# Power.net
KiCad netlist of a schematic drawn in Altium Designer
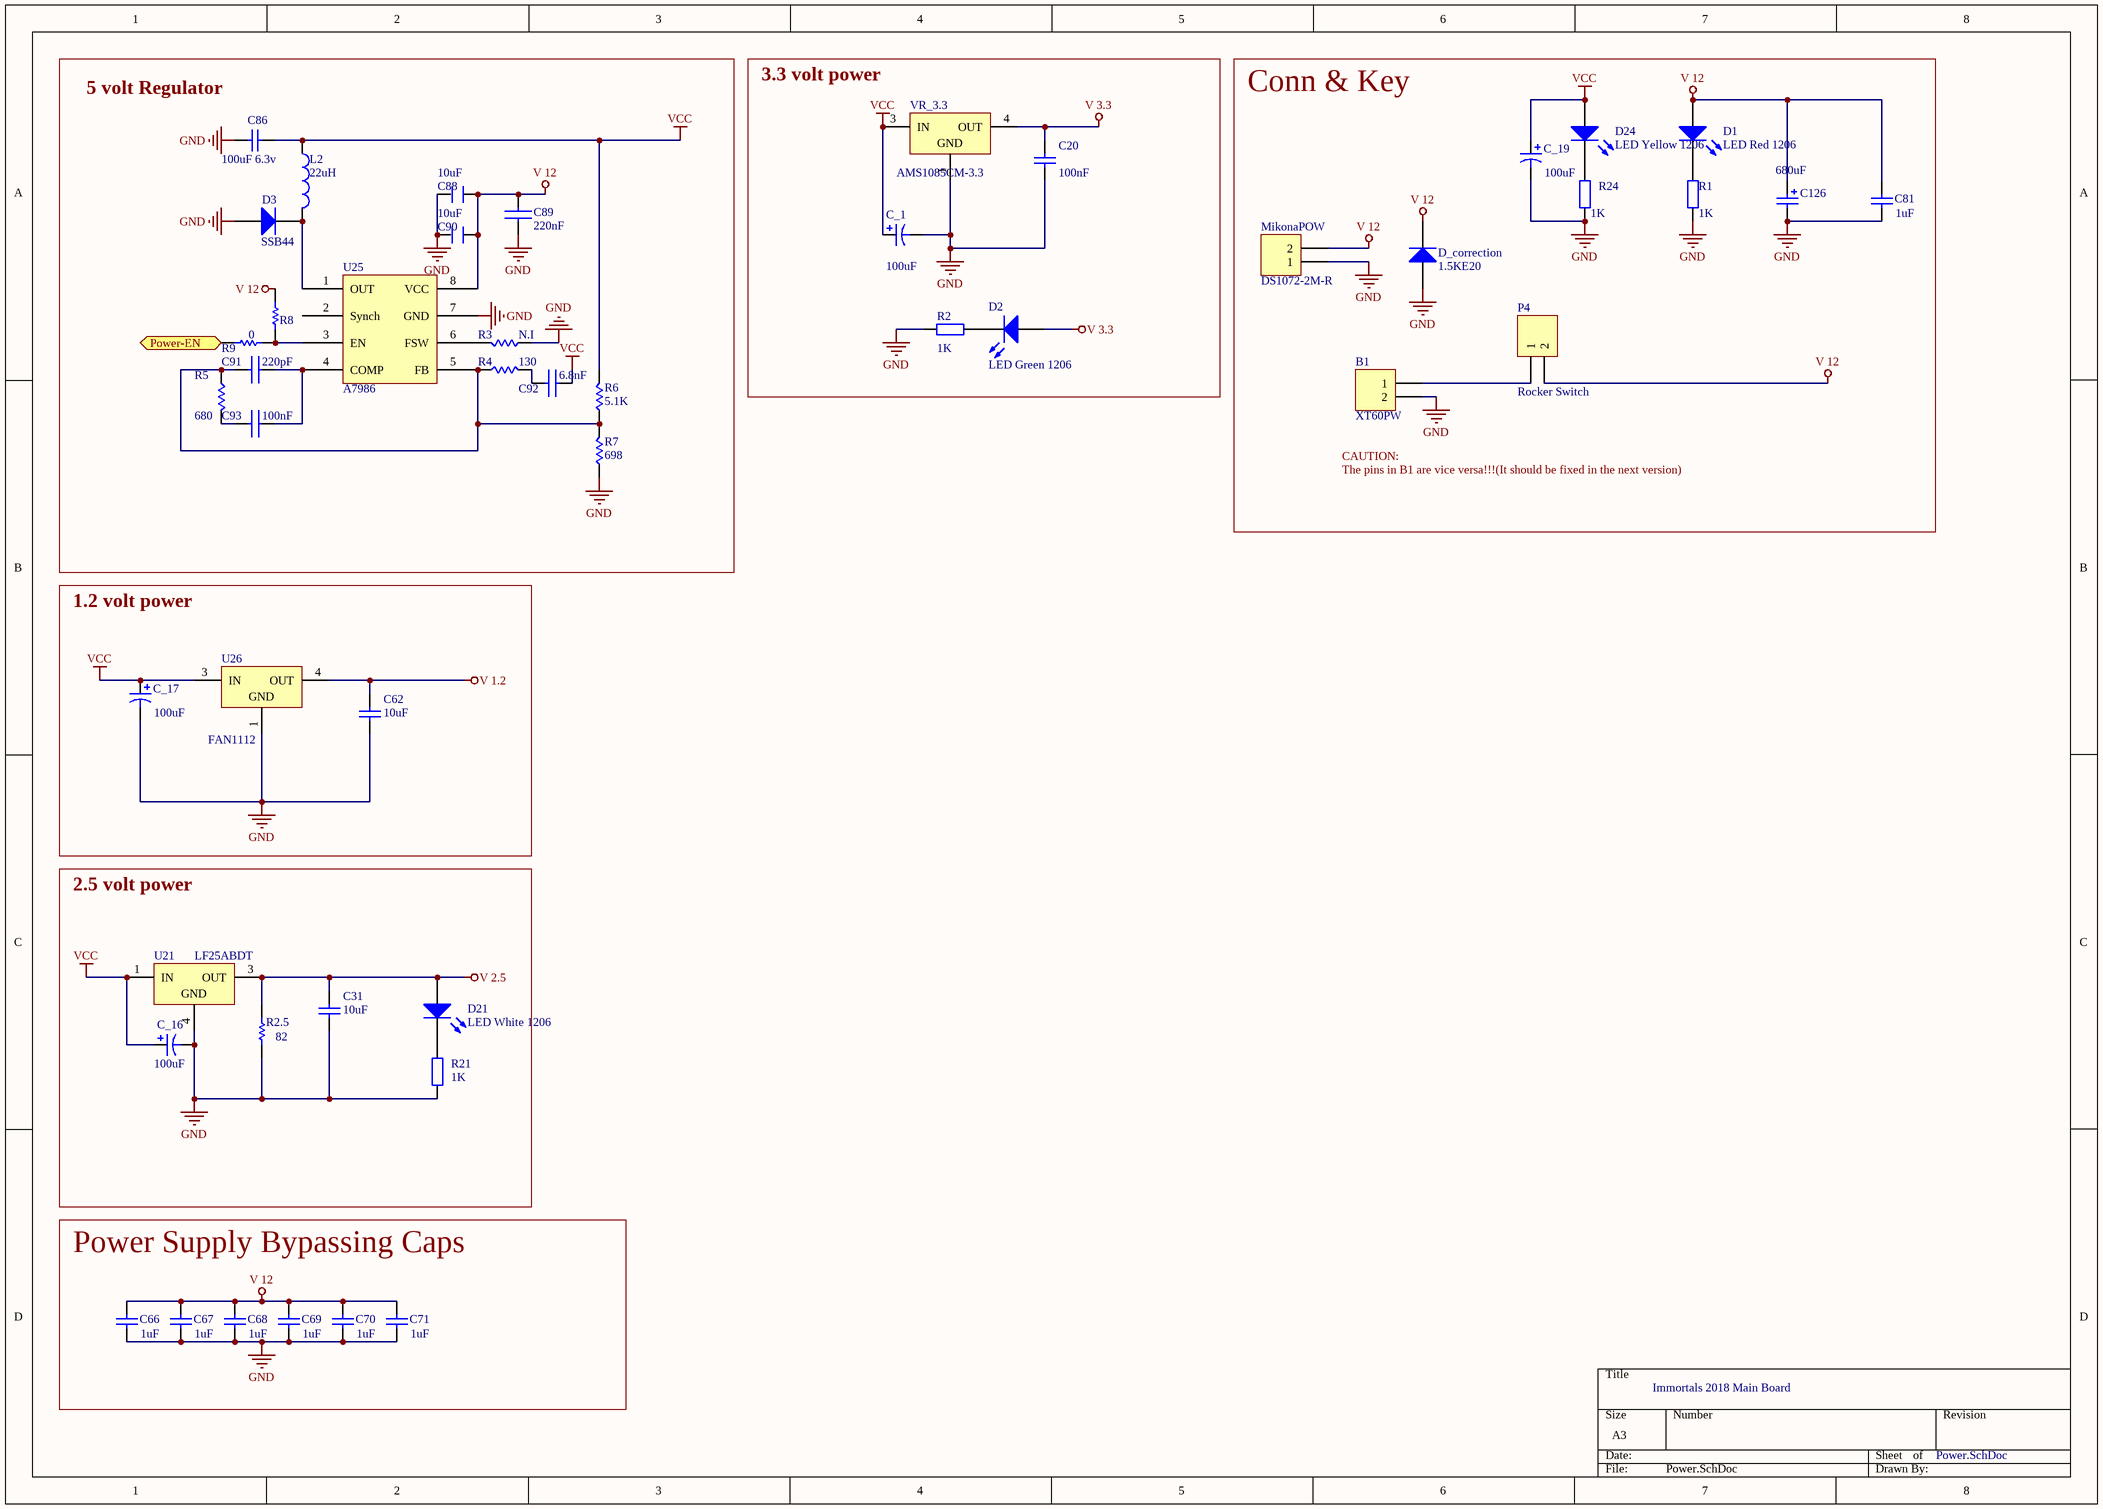
[diagram p0: Power.SchDoc]

(export (version "E")
  (design (tool "Eeschema 10.0.6"))
  (components
    (comp (ref "B1")
      (value "XT60PW")
      (footprint "XT60PW")
      (description "Power Connector")
      (fields (field (name "PUBLISHER") "Altium Limited"))
      (libsource (lib "REV(5)") (part "XT60PW"))
    )
    (comp (ref "C20")
      (value "100nF")
      (footprint "C1206")
      (description "Capacitor (Semiconductor SIM Model)")
      (fields (field (name "Comment") "Cap 100nF 1206") (field (name "PUBLISHER") "Altium Limited"))
      (libsource (lib "Miscellaneous Devices") (part "Cap Semi"))
    )
    (comp (ref "C31")
      (value "10uF")
      (footprint "C1206")
      (description "Capacitor (Semiconductor SIM Model)")
      (fields (field (name "Comment") "Cap 10uF 1206") (field (name "PUBLISHER") "Altium Limited"))
      (libsource (lib "Miscellaneous Devices") (part "Cap Semi"))
    )
    (comp (ref "C62")
      (value "10uF")
      (footprint "C1206")
      (description "Capacitor (Semiconductor SIM Model)")
      (fields (field (name "Comment") "Cap 10uF 1206") (field (name "PUBLISHER") "Altium Limited"))
      (libsource (lib "Miscellaneous Devices") (part "Cap Semi"))
    )
    (comp (ref "C66")
      (value "1uF")
      (footprint "C0805")
      (description "Capacitor")
      (fields (field (name "Comment") "Cap 1uF 0805"))
      (libsource (lib "Altium Nanoboard Project") (part "CAP"))
    )
    (comp (ref "C67")
      (value "1uF")
      (footprint "C0805")
      (description "Capacitor")
      (fields (field (name "Comment") "Cap 1uF 0805"))
      (libsource (lib "Altium Nanoboard Project") (part "CAP"))
    )
    (comp (ref "C68")
      (value "1uF")
      (footprint "C0805")
      (description "Capacitor")
      (fields (field (name "Comment") "Cap 1uF 0805"))
      (libsource (lib "Altium Nanoboard Project") (part "CAP"))
    )
    (comp (ref "C69")
      (value "1uF")
      (footprint "C0805")
      (description "Capacitor")
      (fields (field (name "Comment") "Cap 1uF 0805"))
      (libsource (lib "Altium Nanoboard Project") (part "CAP"))
    )
    (comp (ref "C70")
      (value "1uF")
      (footprint "C0805")
      (description "Capacitor")
      (fields (field (name "Comment") "Cap 1uF 0805"))
      (libsource (lib "Altium Nanoboard Project") (part "CAP"))
    )
    (comp (ref "C71")
      (value "1uF")
      (footprint "C0805")
      (description "Capacitor")
      (fields (field (name "Comment") "Cap 1uF 0805"))
      (libsource (lib "Altium Nanoboard Project") (part "CAP"))
    )
    (comp (ref "C81")
      (value "1uF")
      (footprint "C0805")
      (description "Capacitor")
      (fields (field (name "Comment") "Cap 1uF 0805"))
      (libsource (lib "Altium Nanoboard Project") (part "CAP"))
    )
    (comp (ref "C86")
      (value "100uF 6.3v")
      (footprint "C1210")
      (description "Capacitor (Semiconductor SIM Model)")
      (fields (field (name "Comment") "Cap 100uF 1210") (field (name "PUBLISHER") "Altium Limited"))
      (libsource (lib "Miscellaneous Devices") (part "Cap Semi"))
    )
    (comp (ref "C88")
      (value "10uF")
      (footprint "C[0805]")
      (description "Cap , SMD")
      (fields (field (name "Comment") "Cap 10uF 0805"))
      (libsource (lib "TCU Control") (part "C"))
    )
    (comp (ref "C89")
      (value "220nF")
      (footprint "C0603")
      (description "C0603")
      (fields (field (name "Comment") "Cap 220nF 0603"))
      (libsource (lib "My SMD Lib") (part "Cap 0603"))
    )
    (comp (ref "C90")
      (value "10uF")
      (footprint "C[0805]")
      (description "Cap , SMD")
      (fields (field (name "Comment") "Cap 10uF 0805"))
      (libsource (lib "TCU Control") (part "C"))
    )
    (comp (ref "C91")
      (value "220pF")
      (footprint "C0603")
      (description "C0603")
      (fields (field (name "Comment") "Cap 220pF 0603"))
      (libsource (lib "My SMD Lib") (part "Cap 0603"))
    )
    (comp (ref "C92")
      (value "6.8nF")
      (footprint "C0603")
      (description "C0603")
      (fields (field (name "Comment") "Cap 6.8nF 0603"))
      (libsource (lib "") (part "Cap 0603_1"))
    )
    (comp (ref "C93")
      (value "100nF")
      (footprint "C0603")
      (description "Cap SMD 0603")
      (fields (field (name "Comment") "Cap 100nF 0603"))
      (libsource (lib "My SMD Lib") (part "Cap 0603"))
    )
    (comp (ref "C126")
      (value "680uF")
      (footprint "CAPPR5-5x5")
      (description "Polarized Capacitor (Radial)")
      (fields (field (name "Comment") "Cap 680uF dip") (field (name "PUBLISHER") "Altium Limited"))
      (libsource (lib "REV(5)") (part "Cap Pol1"))
    )
    (comp (ref "C_1")
      (value "100uF")
      (footprint "6332[2512]")
      (description "Polarized Capacitor (Surface Mount)")
      (fields (field (name "Comment") "Cap 100uF 2512") (field (name "PUBLISHER") "Altium Limited"))
      (libsource (lib "Miscellaneous Devices") (part "Cap Pol3"))
    )
    (comp (ref "C_16")
      (value "100uF")
      (footprint "6332[2512]")
      (description "Polarized Capacitor (Surface Mount)")
      (fields (field (name "Comment") "Cap 100uF 2512") (field (name "PUBLISHER") "Altium Limited"))
      (libsource (lib "Miscellaneous Devices") (part "Cap Pol3"))
    )
    (comp (ref "C_17")
      (value "100uF")
      (footprint "6332[2512]")
      (description "Polarized Capacitor (Surface Mount)")
      (fields (field (name "Comment") "Cap 100uF 2512") (field (name "PUBLISHER") "Altium Limited"))
      (libsource (lib "Miscellaneous Devices") (part "Cap Pol3"))
    )
    (comp (ref "C_19")
      (value "100uF")
      (footprint "6332[2512]")
      (description "Polarized Capacitor (Surface Mount)")
      (fields (field (name "Comment") "Cap 100uF 2512") (field (name "PUBLISHER") "Altium Limited"))
      (libsource (lib "Miscellaneous Devices") (part "Cap Pol3"))
    )
    (comp (ref "D1")
      (value "LED Red 1206")
      (footprint "REV(5):3.2X1.6X1.1 - RED")
      (description "Typical RED, GREEN, YELLOW, AMBER GaAs LED")
      (fields (field (name "PUBLISHER") "Altium Limited"))
      (libsource (lib "Miscellaneous Devices") (part "LED2"))
    )
    (comp (ref "D2")
      (value "LED Green 1206")
      (footprint "REV(5):3.2X1.6X1.1 - GREEN")
      (description "Typical RED, GREEN, YELLOW, AMBER GaAs LED")
      (fields (field (name "PUBLISHER") "Altium Limited"))
      (libsource (lib "Miscellaneous Devices") (part "LED2"))
    )
    (comp (ref "D3")
      (value "SSB44")
      (footprint "DIOM4336X24N")
      (description "1 Amp General Purpose Rectifier")
      (fields (field (name "PUBLISHER") "Altium Limited"))
      (libsource (lib "REV(5)") (part "Diode SSB44"))
    )
    (comp (ref "D21")
      (value "LED White 1206")
      (footprint "REV(5):3.2X1.6X1.1 - WHITE")
      (description "Typical RED, GREEN, YELLOW, AMBER GaAs LED")
      (fields (field (name "PUBLISHER") "Altium Limited"))
      (libsource (lib "Miscellaneous Devices") (part "LED2"))
    )
    (comp (ref "D24")
      (value "LED Yellow 1206")
      (footprint "REV(5):3.2X1.6X1.1 - YELLOW")
      (description "Typical RED, GREEN, YELLOW, AMBER GaAs LED")
      (fields (field (name "PUBLISHER") "Altium Limited"))
      (libsource (lib "Miscellaneous Devices") (part "LED2"))
    )
    (comp (ref "D_correction")
      (value "1.5KE20")
      (footprint "DO-41")
      (description "1 Amp General Purpose Rectifier")
      (fields (field (name "PUBLISHER") "Altium Limited"))
      (libsource (lib "REV(5)") (part "Diode 1N4001"))
    )
    (comp (ref "L2")
      (value "22uH")
      (footprint "INDP110100X50N")
      (fields (field (name "Comment") "Inductor 22uH"))
      (libsource (lib "REV(5)") (part "7447714220 WE-PD SMD"))
    )
    (comp (ref "MikonaPOW")
      (value "DS1072-2M-R")
      (footprint "DS1072-2M&F-R")
      (description "Right Angle 3.96mm Power pin")
      (fields (field (name "PUBLISHER") "Altium Limited"))
      (libsource (lib "REV(5)") (part "Header 2"))
    )
    (comp (ref "P4")
      (value "Rocker Switch")
      (footprint "Rocker_SW")
      (description "I/O Power Switch")
      (fields (field (name "PUBLISHER") "Altium Limited"))
      (libsource (lib "REV(5)") (part "Rocker_SW"))
    )
    (comp (ref "R1")
      (value "1K")
      (footprint "2012[0805]")
      (description "Resistor")
      (fields (field (name "Comment") "Res 1K 0805") (field (name "PUBLISHER") "Altium Limited"))
      (libsource (lib "Miscellaneous Devices") (part "Res2"))
    )
    (comp (ref "R2")
      (value "1K")
      (footprint "2012[0805]")
      (description "Resistor")
      (fields (field (name "Comment") "Res 1K 0805") (field (name "PUBLISHER") "Altium Limited"))
      (libsource (lib "") (part "Res2_2"))
    )
    (comp (ref "R2.5")
      (value "82")
      (footprint "3216[1206]")
      (description "Semiconductor Resistor")
      (fields (field (name "Comment") "Res 82 1206") (field (name "PUBLISHER") "Altium Limited"))
      (libsource (lib "Miscellaneous Devices") (part "Res Semi"))
    )
    (comp (ref "R3")
      (value "N.I")
      (footprint "R0603")
      (description "Res 0603")
      (libsource (lib "My SMD Lib") (part "Res 0603"))
    )
    (comp (ref "R4")
      (value "130")
      (footprint "R0603")
      (description "Res 0603")
      (fields (field (name "Comment") "Res 130 0603"))
      (libsource (lib "My SMD Lib") (part "Res 0603"))
    )
    (comp (ref "R5")
      (value "680")
      (footprint "R0603")
      (description "Res 0603")
      (fields (field (name "Comment") "Res 680 0603"))
      (libsource (lib "My SMD Lib") (part "Res 0603"))
    )
    (comp (ref "R6")
      (value "5.1K")
      (footprint "R0603")
      (description "Res 0603")
      (fields (field (name "Comment") "Res 5.1K 0603"))
      (libsource (lib "My SMD Lib") (part "Res 0603"))
    )
    (comp (ref "R7")
      (value "698")
      (footprint "R0603")
      (description "Res 0603")
      (fields (field (name "Comment") "Res 698 0603"))
      (libsource (lib "My SMD Lib") (part "Res 0603"))
    )
    (comp (ref "R8")
      (value "N.I")
      (footprint "R0603")
      (description "Res 0603")
      (libsource (lib "SamatecLib") (part "R0603"))
    )
    (comp (ref "R9")
      (value "0")
      (footprint "R0603")
      (description "Res 0603")
      (fields (field (name "Comment") "Res 0 0603"))
      (libsource (lib "SamatecLib") (part "R0603"))
    )
    (comp (ref "R21")
      (value "1K")
      (footprint "2012[0805]")
      (description "Resistor")
      (fields (field (name "Comment") "Res 1K 0805") (field (name "PUBLISHER") "Altium Limited"))
      (libsource (lib "") (part "Res2_1"))
    )
    (comp (ref "R24")
      (value "1K")
      (footprint "2012[0805]")
      (description "Resistor")
      (fields (field (name "Comment") "Res 1K 0805") (field (name "PUBLISHER") "Altium Limited"))
      (libsource (lib "") (part "Res2_1"))
    )
    (comp (ref "U21")
      (value "LF25ABDT")
      (footprint "TO-252")
      (description "500mA, Very Low Drop (0.45V) Voltage Regulator")
      (fields (field (name "PUBLISHER") "Altium Limited"))
      (libsource (lib "REV(5)") (part "LF25ABDT"))
    )
    (comp (ref "U25")
      (value "A7986")
      (footprint "HSOP8")
      (description "DC\\DC Regulator")
      (libsource (lib "SamatecLib") (part "A7986"))
    )
    (comp (ref "U26")
      (value "FAN1112")
      (footprint "TO-252")
      (description "500mA, Very Low Drop (0.45V) Voltage Regulator")
      (fields (field (name "PUBLISHER") "Altium Limited"))
      (libsource (lib "REV(5)") (part "FAN1112"))
    )
    (comp (ref "VR_3.3")
      (value "AMS1085CM-3.3")
      (footprint "936-03")
      (description "5A Low Dropout Fast Response Positive Fixed Voltage Regulator")
      (fields (field (name "PUBLISHER") "Altium Limited"))
      (libsource (lib "REV(5)") (part "LT1585ACM-1.5"))
    )
  )
  (nets
    (net (code "1") (name "/Power-EN") (class "Default")
      (node (ref "R9") (pin "1") (pinfunction "1_1") (pintype "passive"))
    )
    (net (code "2") (name "GND") (class "Default")
      (node (ref "B1") (pin "2") (pinfunction "2_2") (pintype "passive"))
      (node (ref "C126") (pin "2") (pinfunction "2_2") (pintype "passive"))
      (node (ref "C20") (pin "2") (pinfunction "2_2") (pintype "passive"))
      (node (ref "C31") (pin "1") (pinfunction "1_1") (pintype "passive"))
      (node (ref "C62") (pin "1") (pinfunction "1_1") (pintype "passive"))
      (node (ref "C66") (pin "2") (pinfunction "2_2") (pintype "passive"))
      (node (ref "C67") (pin "2") (pinfunction "2_2") (pintype "passive"))
      (node (ref "C68") (pin "2") (pinfunction "2_2") (pintype "passive"))
      (node (ref "C69") (pin "2") (pinfunction "2_2") (pintype "passive"))
      (node (ref "C70") (pin "2") (pinfunction "2_2") (pintype "passive"))
      (node (ref "C71") (pin "2") (pinfunction "2_2") (pintype "passive"))
      (node (ref "C81") (pin "2") (pinfunction "2_2") (pintype "passive"))
      (node (ref "C86") (pin "1") (pinfunction "1_1") (pintype "passive"))
      (node (ref "C88") (pin "2") (pinfunction "2_2") (pintype "passive"))
      (node (ref "C89") (pin "2") (pinfunction "2_2") (pintype "passive"))
      (node (ref "C90") (pin "2") (pinfunction "2_2") (pintype "passive"))
      (node (ref "C_1") (pin "2") (pinfunction "2_2") (pintype "passive"))
      (node (ref "C_16") (pin "2") (pinfunction "2_2") (pintype "passive"))
      (node (ref "C_17") (pin "2") (pinfunction "2_2") (pintype "passive"))
      (node (ref "C_19") (pin "2") (pinfunction "2_2") (pintype "passive"))
      (node (ref "D3") (pin "2") (pinfunction "A_2") (pintype "passive"))
      (node (ref "D_correction") (pin "1") (pinfunction "A_1") (pintype "passive"))
      (node (ref "MikonaPOW") (pin "1") (pinfunction "1_1") (pintype "passive"))
      (node (ref "R1") (pin "2") (pinfunction "2_2") (pintype "passive"))
      (node (ref "R2") (pin "1") (pinfunction "1_1") (pintype "passive"))
      (node (ref "R2.5") (pin "1") (pinfunction "1_1") (pintype "passive"))
      (node (ref "R21") (pin "1") (pinfunction "1_1") (pintype "passive"))
      (node (ref "R24") (pin "1") (pinfunction "1_1") (pintype "passive"))
      (node (ref "R3") (pin "1") (pinfunction "1_1") (pintype "passive"))
      (node (ref "R7") (pin "1") (pinfunction "1_1") (pintype "passive"))
      (node (ref "U21") (pin "4") (pinfunction "GND_4") (pintype "power_in"))
      (node (ref "U25") (pin "7") (pinfunction "GND_7") (pintype "passive"))
      (node (ref "U26") (pin "1") (pinfunction "GND_1") (pintype "power_in"))
      (node (ref "VR_3.3") (pin "1") (pinfunction "GND_1") (pintype "power_in"))
    )
    (net (code "3") (name "Net-(B1-Pad1)") (class "Default")
      (node (ref "B1") (pin "1") (pinfunction "1_1") (pintype "passive"))
      (node (ref "P4") (pin "1") (pinfunction "1_1") (pintype "passive"))
    )
    (net (code "4") (name "Net-(C92-1-Pad2)") (class "Default")
      (node (ref "C92") (pin "2") (pinfunction "1_2") (pintype "passive"))
      (node (ref "R4") (pin "2") (pinfunction "2_2") (pintype "passive"))
    )
    (net (code "5") (name "Net-(C93-Pad1)") (class "Default")
      (node (ref "C93") (pin "1") (pinfunction "1_1") (pintype "passive"))
      (node (ref "R5") (pin "2") (pinfunction "2_2") (pintype "passive"))
    )
    (net (code "6") (name "Net-(D1-K)") (class "Default")
      (node (ref "D1") (pin "2") (pinfunction "K_2") (pintype "passive"))
      (node (ref "R1") (pin "1") (pinfunction "1_1") (pintype "passive"))
    )
    (net (code "7") (name "Net-(D2-K)") (class "Default")
      (node (ref "D2") (pin "2") (pinfunction "K_2") (pintype "passive"))
      (node (ref "R2") (pin "2") (pinfunction "2_2") (pintype "passive"))
    )
    (net (code "8") (name "Net-(D3-K)") (class "Default")
      (node (ref "D3") (pin "1") (pinfunction "K_1") (pintype "passive"))
      (node (ref "L2") (pin "2") (pinfunction "2_2") (pintype "passive"))
      (node (ref "U25") (pin "1") (pinfunction "OUT_1") (pintype "passive"))
    )
    (net (code "9") (name "Net-(D21-K)") (class "Default")
      (node (ref "D21") (pin "2") (pinfunction "K_2") (pintype "passive"))
      (node (ref "R21") (pin "2") (pinfunction "2_2") (pintype "passive"))
    )
    (net (code "10") (name "Net-(D24-K)") (class "Default")
      (node (ref "D24") (pin "2") (pinfunction "K_2") (pintype "passive"))
      (node (ref "R24") (pin "2") (pinfunction "2_2") (pintype "passive"))
    )
    (net (code "11") (name "Net-(U25-COMP)") (class "Default")
      (node (ref "C91") (pin "2") (pinfunction "2_2") (pintype "passive"))
      (node (ref "C93") (pin "2") (pinfunction "2_2") (pintype "passive"))
      (node (ref "U25") (pin "4") (pinfunction "COMP_4") (pintype "passive"))
    )
    (net (code "12") (name "Net-(U25-EN)") (class "Default")
      (node (ref "R8") (pin "2") (pinfunction "2_2") (pintype "passive"))
      (node (ref "R9") (pin "2") (pinfunction "2_2") (pintype "passive"))
      (node (ref "U25") (pin "3") (pinfunction "EN_3") (pintype "passive"))
    )
    (net (code "13") (name "Net-(U25-FB)") (class "Default")
      (node (ref "C91") (pin "1") (pinfunction "1_1") (pintype "passive"))
      (node (ref "R4") (pin "1") (pinfunction "1_1") (pintype "passive"))
      (node (ref "R5") (pin "1") (pinfunction "1_1") (pintype "passive"))
      (node (ref "R6") (pin "1") (pinfunction "1_1") (pintype "passive"))
      (node (ref "R7") (pin "2") (pinfunction "2_2") (pintype "passive"))
      (node (ref "U25") (pin "5") (pinfunction "FB_5") (pintype "passive"))
    )
    (net (code "14") (name "Net-(U25-FSW)") (class "Default")
      (node (ref "R3") (pin "2") (pinfunction "2_2") (pintype "passive"))
      (node (ref "U25") (pin "6") (pinfunction "FSW_6") (pintype "passive"))
    )
    (net (code "15") (name "V 1.2") (class "Default")
      (node (ref "C62") (pin "2") (pinfunction "2_2") (pintype "passive"))
      (node (ref "U26") (pin "4") (pinfunction "OUT_4") (pintype "power_in"))
    )
    (net (code "16") (name "V 2.5") (class "Default")
      (node (ref "C31") (pin "2") (pinfunction "2_2") (pintype "passive"))
      (node (ref "D21") (pin "1") (pinfunction "A_1") (pintype "passive"))
      (node (ref "R2.5") (pin "2") (pinfunction "2_2") (pintype "passive"))
      (node (ref "U21") (pin "3") (pinfunction "OUT_3") (pintype "power_in"))
    )
    (net (code "17") (name "V 3.3") (class "Default")
      (node (ref "C20") (pin "1") (pinfunction "1_1") (pintype "passive"))
      (node (ref "D2") (pin "1") (pinfunction "A_1") (pintype "passive"))
      (node (ref "VR_3.3") (pin "4") (pinfunction "OUT_4") (pintype "power_in"))
    )
    (net (code "18") (name "V 12") (class "Default")
      (node (ref "C126") (pin "1") (pinfunction "1_1") (pintype "passive"))
      (node (ref "C66") (pin "1") (pinfunction "1_1") (pintype "passive"))
      (node (ref "C67") (pin "1") (pinfunction "1_1") (pintype "passive"))
      (node (ref "C68") (pin "1") (pinfunction "1_1") (pintype "passive"))
      (node (ref "C69") (pin "1") (pinfunction "1_1") (pintype "passive"))
      (node (ref "C70") (pin "1") (pinfunction "1_1") (pintype "passive"))
      (node (ref "C71") (pin "1") (pinfunction "1_1") (pintype "passive"))
      (node (ref "C81") (pin "1") (pinfunction "1_1") (pintype "passive"))
      (node (ref "C88") (pin "1") (pinfunction "1_1") (pintype "passive"))
      (node (ref "C89") (pin "1") (pinfunction "1_1") (pintype "passive"))
      (node (ref "C90") (pin "1") (pinfunction "1_1") (pintype "passive"))
      (node (ref "D1") (pin "1") (pinfunction "A_1") (pintype "passive"))
      (node (ref "D_correction") (pin "2") (pinfunction "K_2") (pintype "passive"))
      (node (ref "MikonaPOW") (pin "2") (pinfunction "2_2") (pintype "passive"))
      (node (ref "P4") (pin "2") (pinfunction "2_2") (pintype "passive"))
      (node (ref "R8") (pin "1") (pinfunction "1_1") (pintype "passive"))
      (node (ref "U25") (pin "8") (pinfunction "VCC_8") (pintype "passive"))
    )
    (net (code "19") (name "VCC") (class "Default")
      (node (ref "C86") (pin "2") (pinfunction "2_2") (pintype "passive"))
      (node (ref "C92") (pin "1") (pinfunction "1_1") (pintype "passive"))
      (node (ref "C_1") (pin "1") (pinfunction "1_1") (pintype "passive"))
      (node (ref "C_16") (pin "1") (pinfunction "1_1") (pintype "passive"))
      (node (ref "C_17") (pin "1") (pinfunction "1_1") (pintype "passive"))
      (node (ref "C_19") (pin "1") (pinfunction "1_1") (pintype "passive"))
      (node (ref "D24") (pin "1") (pinfunction "A_1") (pintype "passive"))
      (node (ref "L2") (pin "1") (pinfunction "1_1") (pintype "passive"))
      (node (ref "R6") (pin "2") (pinfunction "2_2") (pintype "passive"))
      (node (ref "U21") (pin "1") (pinfunction "IN_1") (pintype "power_in"))
      (node (ref "U26") (pin "3") (pinfunction "IN_3") (pintype "power_in"))
      (node (ref "VR_3.3") (pin "3") (pinfunction "IN_3") (pintype "power_in"))
    )
    (net (code "20") (name "unconnected-(U25-Synch-Pad2)") (class "Default")
      (node (ref "U25") (pin "2") (pinfunction "Synch_2") (pintype "passive"))
    )
  )
)
